# CURRENT_IN.net
KiCad netlist of a schematic drawn in Altium Designer
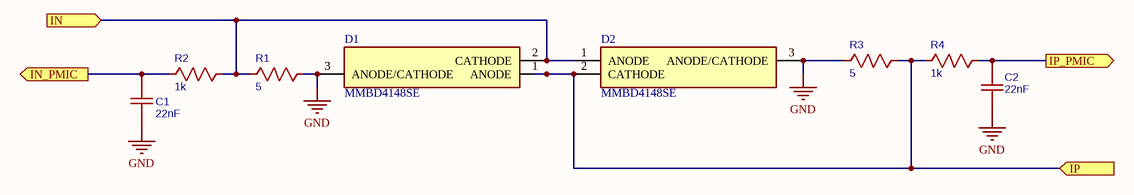
[diagram p0: CURRENT_IN.SchDoc]

(export (version "E")
  (design (tool "Eeschema 10.0.6"))
  (components
    (comp (ref "C1")
      (value "22nF")
      (footprint "GRM31C5C1E104GA01L:CAPC3216X190")
      (libsource (lib "altium-import") (part "root_0_22nF_"))
    )
    (comp (ref "C2")
      (value "22nF")
      (footprint "GRM31C5C1E104GA01L:CAPC3216X190")
      (libsource (lib "altium-import") (part "root_0_22nF_"))
    )
    (comp (ref "D1")
      (value "MMBD4148SE")
      (footprint "SamacSys:SOT95P240X120-3N")
      (description "Diode")
      (fields (field (name "MOUSER PART NUMBER") "512-MMBD4148SE"))
      (libsource (lib "") (part "MMBD4148SE_1"))
    )
    (comp (ref "D2")
      (value "MMBD4148SE")
      (footprint "SamacSys:SOT95P240X120-3N")
      (description "Diode")
      (fields (field (name "MOUSER PART NUMBER") "512-MMBD4148SE"))
      (libsource (lib "*") (part "MMBD4148SE"))
    )
    (comp (ref "R1")
      (value "5")
      (footprint "SamacSys:RESC3216X75N")
      (libsource (lib "altium-import") (part "root_0_1k_"))
    )
    (comp (ref "R2")
      (value "1k")
      (footprint "SamacSys:RESC3216X75N")
      (libsource (lib "altium-import") (part "root_0_1k_"))
    )
    (comp (ref "R3")
      (value "5")
      (footprint "SamacSys:RESC3216X75N")
      (libsource (lib "altium-import") (part "root_0_1k_"))
    )
    (comp (ref "R4")
      (value "1k")
      (footprint "SamacSys:RESC3216X75N")
      (libsource (lib "altium-import") (part "root_0_1k_"))
    )
  )
  (nets
    (net (code "1") (name "/IN") (class "Default")
      (node (ref "D1") (pin "2") (pinfunction "CATHODE_2") (pintype "passive"))
      (node (ref "D2") (pin "1") (pinfunction "ANODE_1") (pintype "passive"))
      (node (ref "R1") (pin "1") (pinfunction "1_1") (pintype "passive"))
      (node (ref "R2") (pin "2") (pinfunction "2_2") (pintype "passive"))
    )
    (net (code "2") (name "/IN_PMIC") (class "Default")
      (node (ref "C1") (pin "2") (pinfunction "2_2") (pintype "passive"))
      (node (ref "R2") (pin "1") (pinfunction "1_1") (pintype "passive"))
    )
    (net (code "3") (name "/IP") (class "Default")
      (node (ref "D1") (pin "1") (pinfunction "ANODE_1") (pintype "passive"))
      (node (ref "D2") (pin "2") (pinfunction "CATHODE_2") (pintype "passive"))
      (node (ref "R3") (pin "2") (pinfunction "2_2") (pintype "passive"))
      (node (ref "R4") (pin "1") (pinfunction "1_1") (pintype "passive"))
    )
    (net (code "4") (name "/IP_PMIC") (class "Default")
      (node (ref "C2") (pin "2") (pinfunction "2_2") (pintype "passive"))
      (node (ref "R4") (pin "2") (pinfunction "2_2") (pintype "passive"))
    )
    (net (code "5") (name "GND") (class "Default")
      (node (ref "C1") (pin "1") (pinfunction "1_1") (pintype "passive"))
      (node (ref "C2") (pin "1") (pinfunction "1_1") (pintype "passive"))
      (node (ref "D1") (pin "3") (pinfunction "ANODE/CATHODE_3") (pintype "passive"))
      (node (ref "D2") (pin "3") (pinfunction "ANODE/CATHODE_3") (pintype "passive"))
      (node (ref "R1") (pin "2") (pinfunction "2_2") (pintype "passive"))
      (node (ref "R3") (pin "1") (pinfunction "1_1") (pintype "passive"))
    )
  )
)
